# iridia-tam-main-board.net
KiCad netlist of a schematic drawn in EAGLE
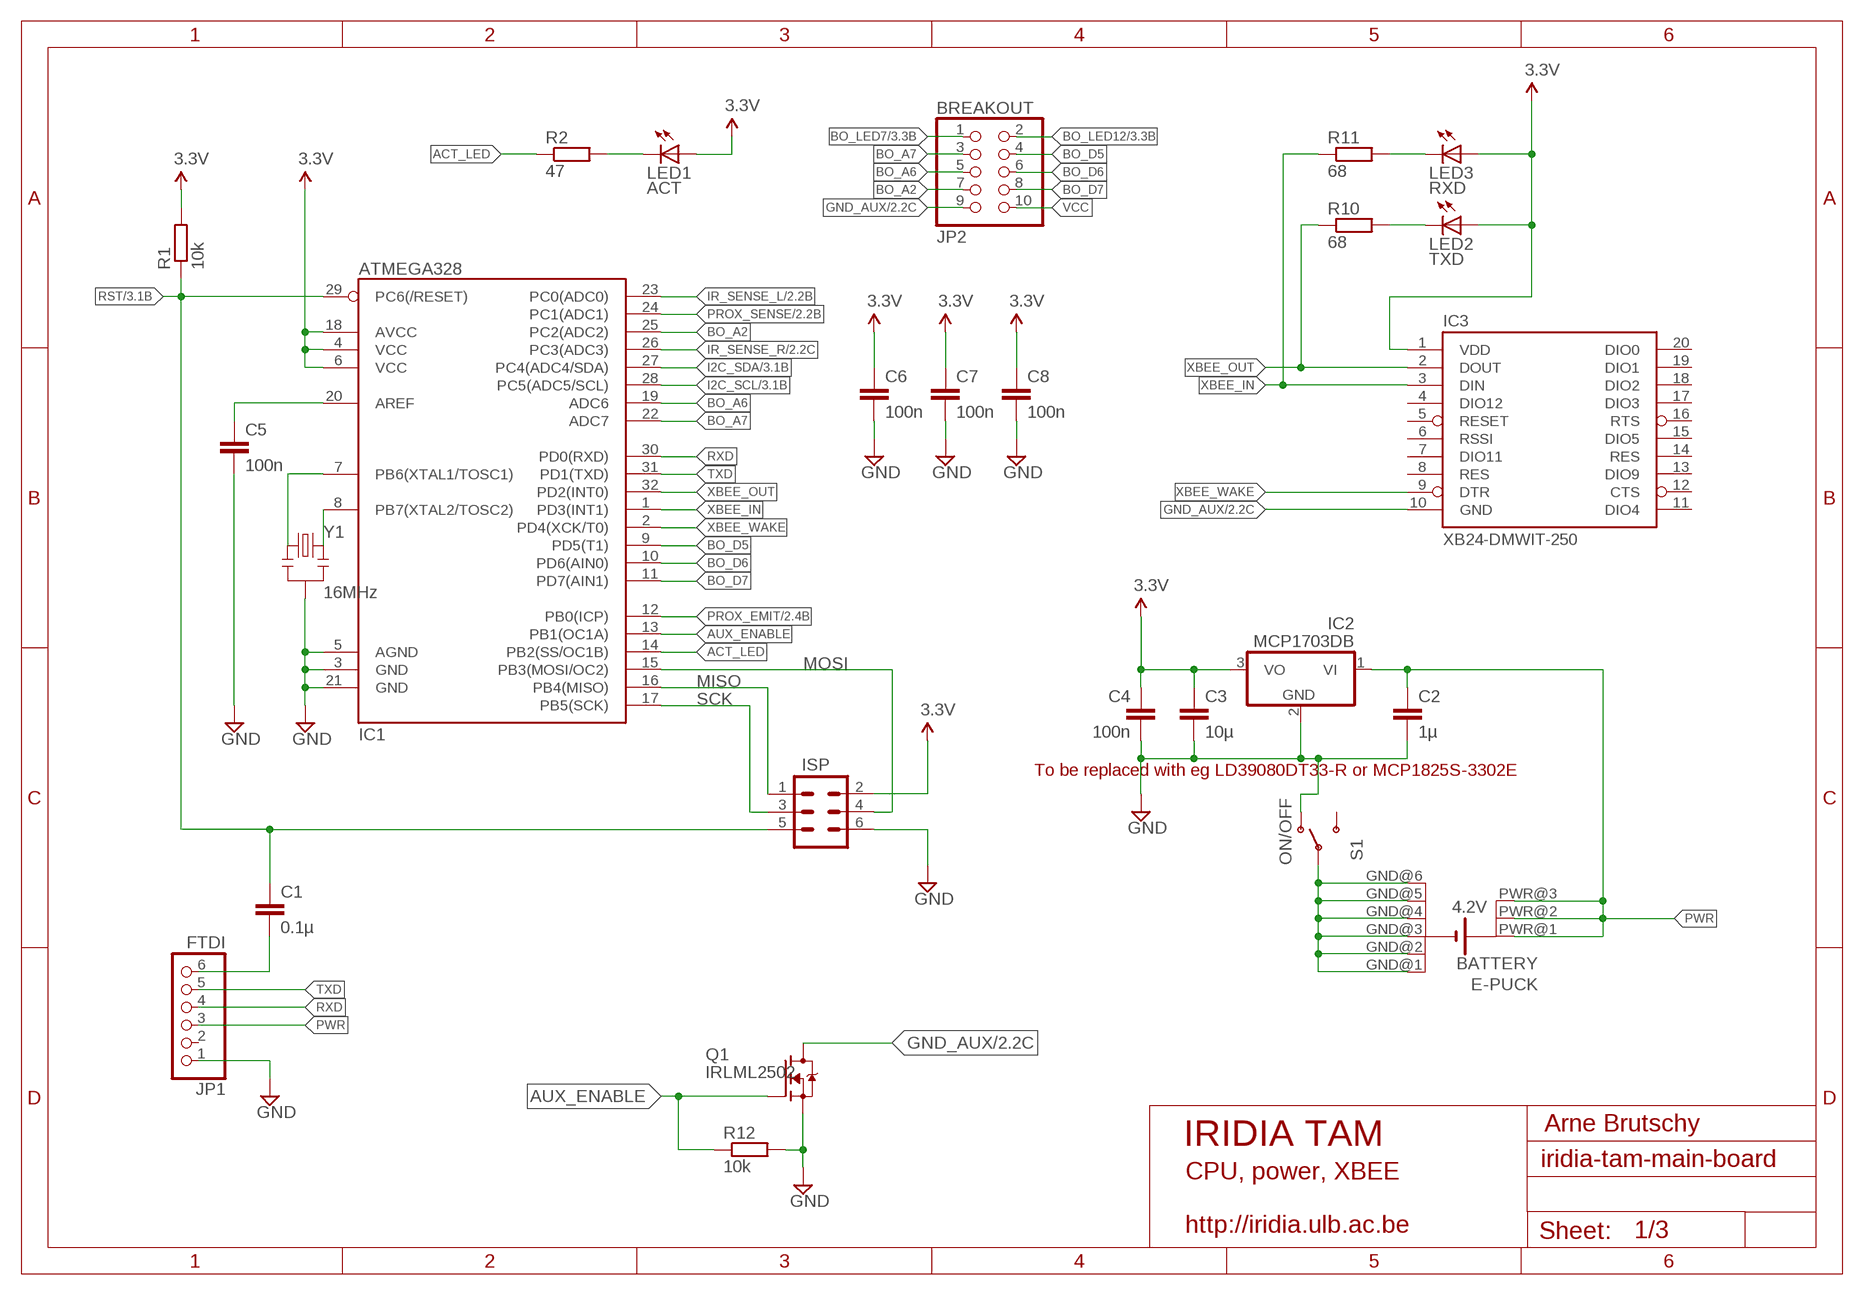
[diagram p0: schematic, sheet 1]
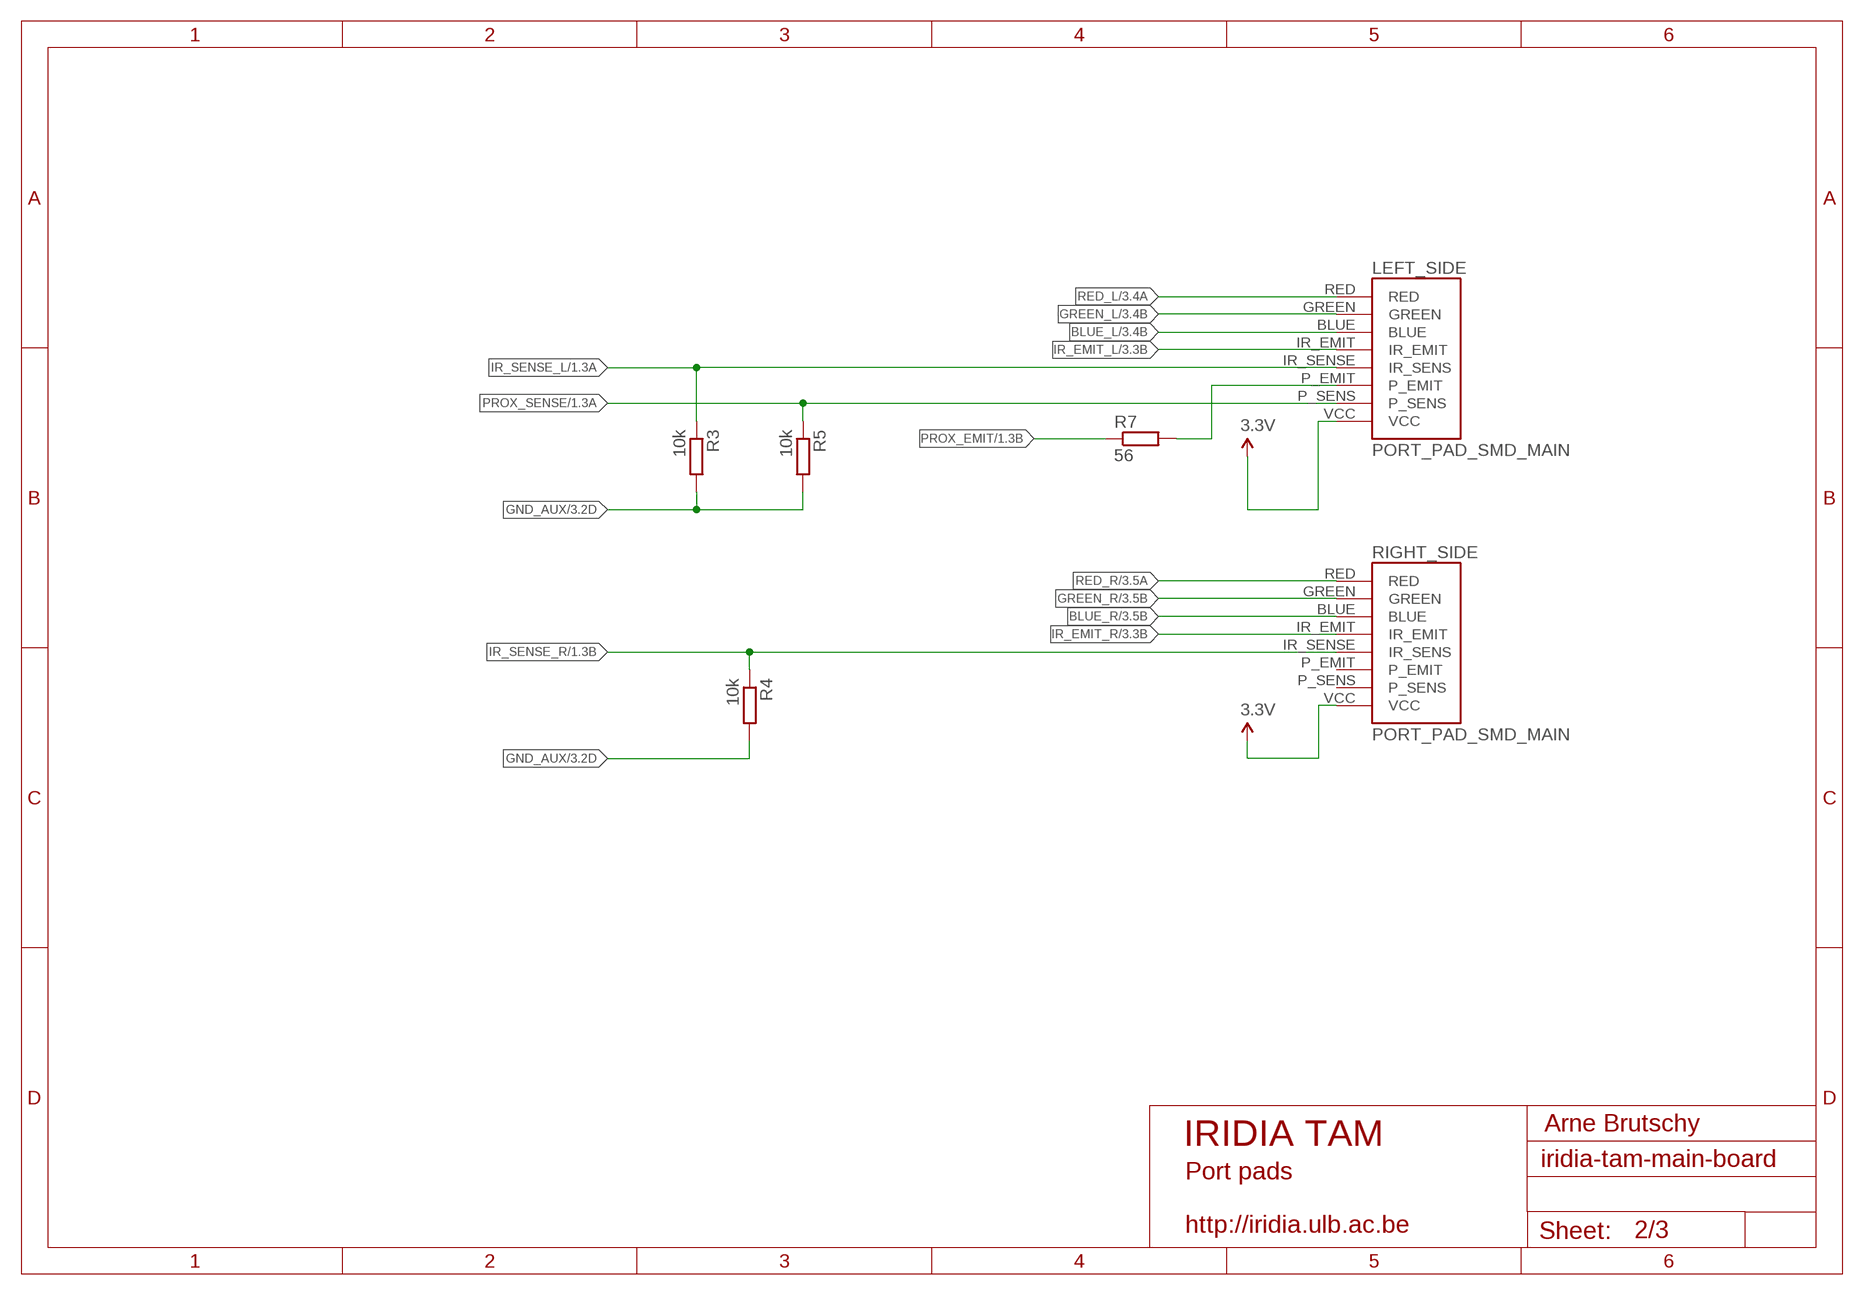
[diagram p1: schematic, sheet 2]
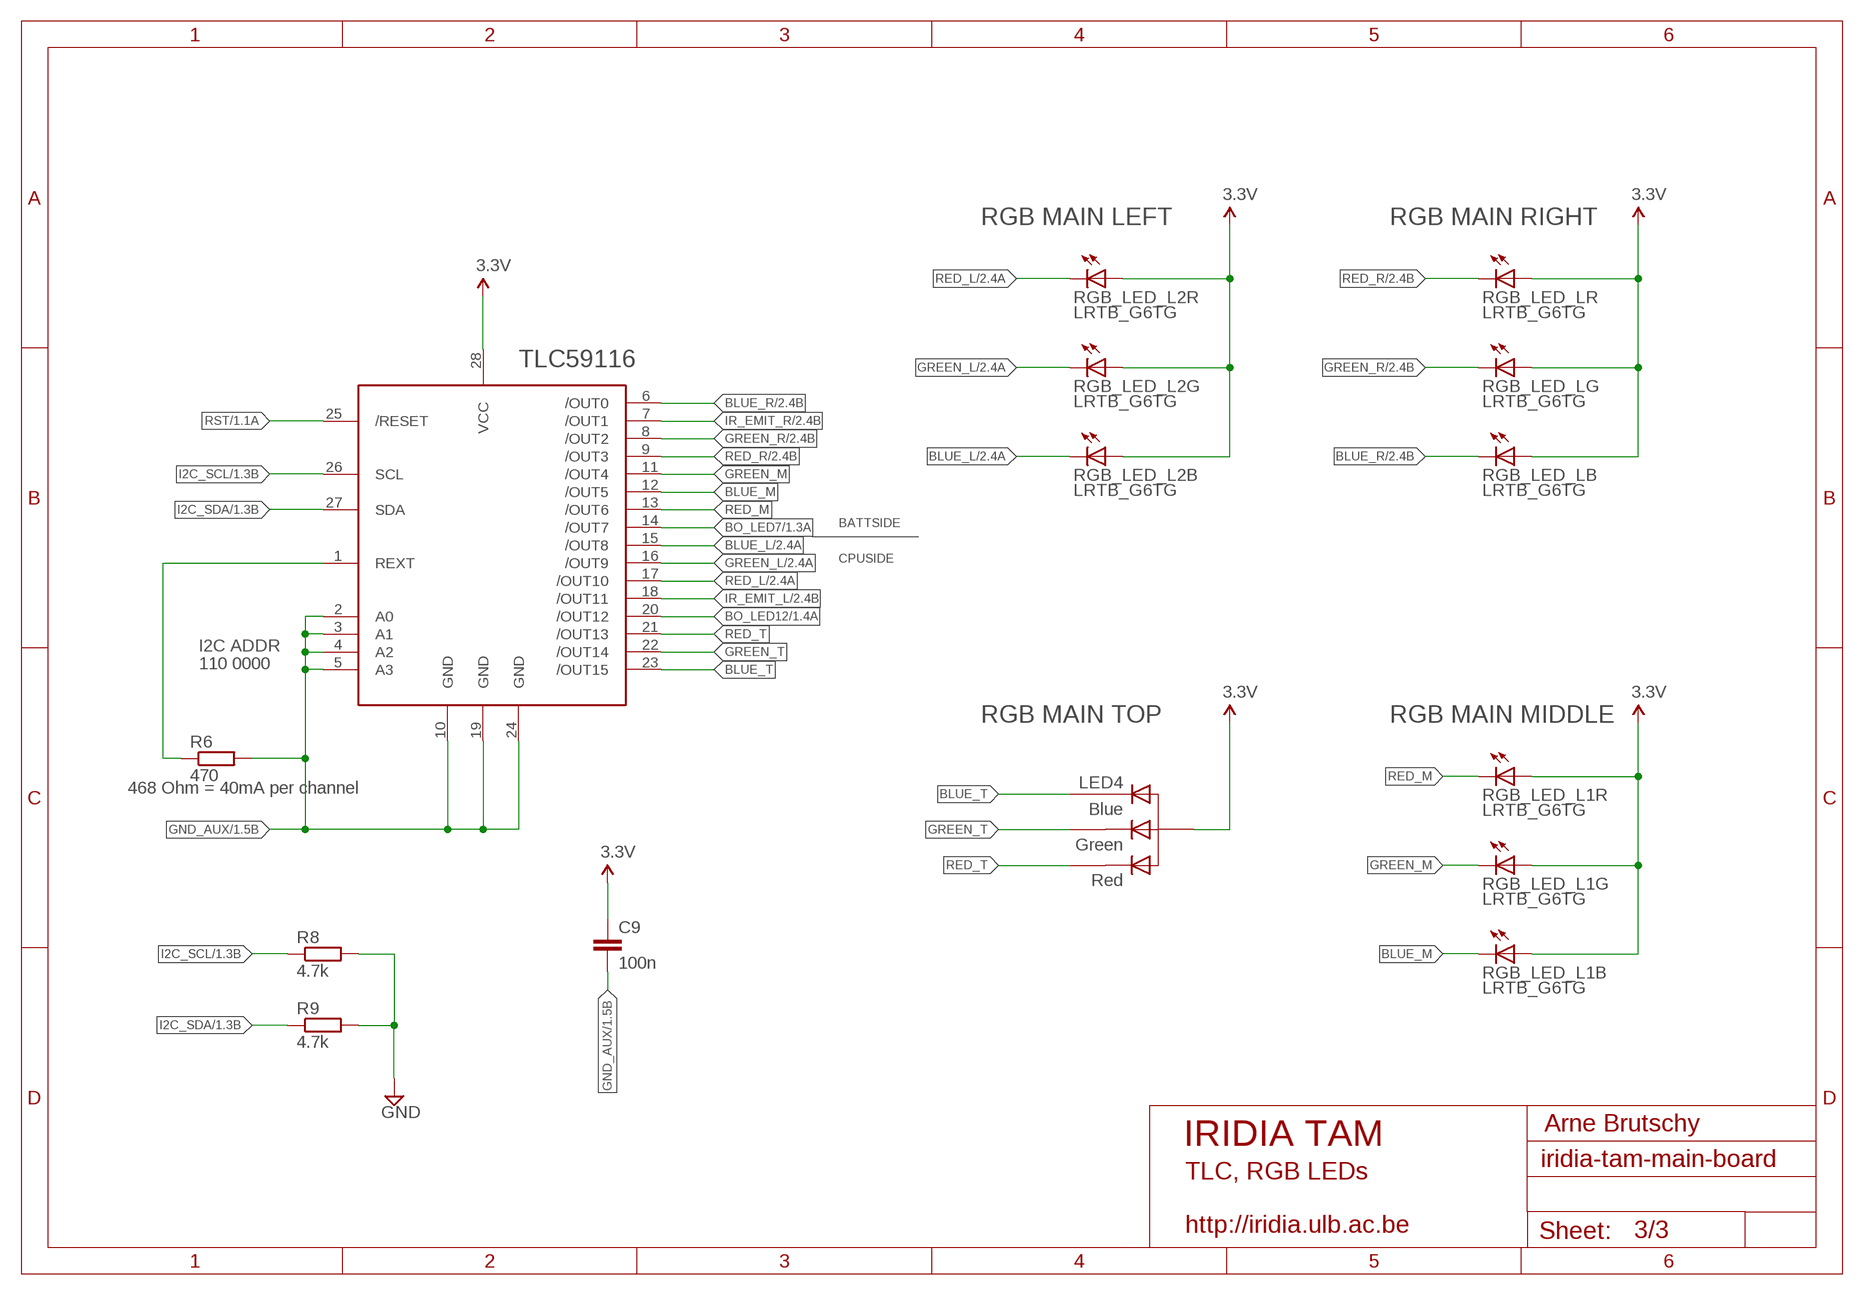
[diagram p2: schematic, sheet 3]

(export (version "E")
  (design (tool "Eeschema 10.0.6"))
  (components
    (comp (ref "C9")
      (value "100n")
      (footprint "eagle-import:0805")
      (libsource (lib "eagle-import") (part "CAP0805"))
    )
    (comp (ref "IC4")
      (value "TLC59116")
      (footprint "eagle-import:TSSOP28")
      (libsource (lib "eagle-import") (part "TLC59116"))
    )
    (comp (ref "LED4")
      (value "RGBLED_CA5MMTROUGHHOLE")
      (footprint "eagle-import:LED5MMRGB")
      (libsource (lib "eagle-import") (part "RGBLED_CA5MMTROUGHHOLE"))
    )
    (comp (ref "R6")
      (value "470")
      (footprint "eagle-import:R0805")
      (libsource (lib "eagle-import") (part "R-EU_R0805"))
    )
    (comp (ref "R8")
      (value "4.7k")
      (footprint "eagle-import:R0805")
      (libsource (lib "eagle-import") (part "R-EU_R0805"))
    )
    (comp (ref "R9")
      (value "4.7k")
      (footprint "eagle-import:R0805")
      (libsource (lib "eagle-import") (part "R-EU_R0805"))
    )
    (comp (ref "RGB_LED_L")
      (value "LRTB_G6TG")
      (footprint "eagle-import:P-LCC-6_TOPLED")
      (libsource (lib "eagle-import") (part "MULTILED_LRTB_G6TG"))
    )
    (comp (ref "RGB_LED_L1")
      (value "LRTB_G6TG")
      (footprint "eagle-import:P-LCC-6_TOPLED")
      (libsource (lib "eagle-import") (part "MULTILED_LRTB_G6TG"))
    )
    (comp (ref "RGB_LED_L2")
      (value "LRTB_G6TG")
      (footprint "eagle-import:P-LCC-6_TOPLED")
      (libsource (lib "eagle-import") (part "MULTILED_LRTB_G6TG"))
    )
    (comp (ref "BREAKOUT")
      (value "JP2")
      (footprint "eagle-import:2X05SMD")
      (libsource (lib "eagle-import") (part "PINHD-2X5_2.54-SMD"))
    )
    (comp (ref "C1")
      (value "0.1µ")
      (footprint "eagle-import:0805")
      (libsource (lib "eagle-import") (part "CAP0805"))
    )
    (comp (ref "C2")
      (value "1µ")
      (footprint "eagle-import:0805")
      (libsource (lib "eagle-import") (part "CAP0805"))
    )
    (comp (ref "C3")
      (value "10µ")
      (footprint "eagle-import:0805")
      (libsource (lib "eagle-import") (part "CAP0805"))
    )
    (comp (ref "C4")
      (value "100n")
      (footprint "eagle-import:0805")
      (libsource (lib "eagle-import") (part "CAP0805"))
    )
    (comp (ref "C5")
      (value "100n")
      (footprint "eagle-import:0805")
      (libsource (lib "eagle-import") (part "CAP0805"))
    )
    (comp (ref "C6")
      (value "100n")
      (footprint "eagle-import:0805")
      (libsource (lib "eagle-import") (part "CAP0805"))
    )
    (comp (ref "C7")
      (value "100n")
      (footprint "eagle-import:0805")
      (libsource (lib "eagle-import") (part "CAP0805"))
    )
    (comp (ref "C8")
      (value "100n")
      (footprint "eagle-import:0805")
      (libsource (lib "eagle-import") (part "CAP0805"))
    )
    (comp (ref "IC1")
      (value "ATMEGA328")
      (footprint "eagle-import:TQFP32-08")
      (libsource (lib "eagle-import") (part "ATMEGA168"))
    )
    (comp (ref "IC2")
      (value "MCP1703DB")
      (footprint "eagle-import:SOT223")
      (libsource (lib "eagle-import") (part "MCP1703DB"))
    )
    (comp (ref "IC3")
      (value "XB24-DMWIT-250")
      (footprint "eagle-import:XBEE-SMD")
      (libsource (lib "eagle-import") (part "XBEE-1B3"))
    )
    (comp (ref "JP1")
      (value "FTDI")
      (footprint "eagle-import:1X06SMD_90")
      (libsource (lib "eagle-import") (part "PINHD-1X6_2.54-SMD-90°"))
    )
    (comp (ref "LED1")
      (value "ACT")
      (footprint "eagle-import:LED-1206")
      (libsource (lib "eagle-import") (part "LED1206"))
    )
    (comp (ref "LED2")
      (value "TXD")
      (footprint "eagle-import:CHIPLED_0805")
      (libsource (lib "eagle-import") (part "LEDCHIPLED_0805"))
    )
    (comp (ref "LED3")
      (value "RXD")
      (footprint "eagle-import:CHIPLED_0805")
      (libsource (lib "eagle-import") (part "LEDCHIPLED_0805"))
    )
    (comp (ref "Q1")
      (value "IRLML2502")
      (footprint "eagle-import:SOT23-3")
      (libsource (lib "eagle-import") (part "IRLML2502"))
    )
    (comp (ref "R1")
      (value "10k")
      (footprint "eagle-import:R0805")
      (libsource (lib "eagle-import") (part "R-EU_R0805"))
    )
    (comp (ref "R2")
      (value "47")
      (footprint "eagle-import:R0805")
      (libsource (lib "eagle-import") (part "R-EU_R0805"))
    )
    (comp (ref "R10")
      (value "68")
      (footprint "eagle-import:R0805")
      (libsource (lib "eagle-import") (part "R-EU_R0805"))
    )
    (comp (ref "R11")
      (value "68")
      (footprint "eagle-import:R0805")
      (libsource (lib "eagle-import") (part "R-EU_R0805"))
    )
    (comp (ref "R12")
      (value "10k")
      (footprint "eagle-import:R0805")
      (libsource (lib "eagle-import") (part "R-EU_R0805"))
    )
    (comp (ref "S1")
      (value "ON/OFF")
      (footprint "eagle-import:200USP1T1A1M6RE")
      (libsource (lib "eagle-import") (part "TOGGLESW200MSP1T2B2M6RE"))
    )
    (comp (ref "SV1")
      (value "ISP")
      (footprint "eagle-import:MA03-2")
      (libsource (lib "eagle-import") (part "MA03-2"))
    )
    (comp (ref "U$4")
      (value "EPUCK_BATTERY")
      (footprint "eagle-import:EPUCK_BATTERY")
      (libsource (lib "eagle-import") (part "EPUCK_BATTERY"))
    )
    (comp (ref "Y1")
      (value "16MHz")
      (footprint "eagle-import:RESONATOR-SMD")
      (libsource (lib "eagle-import") (part "RESONATOR16MHZ"))
    )
    (comp (ref "LEFT_SIDE")
      (value "PORT_PAD_SMD_MAIN")
      (footprint "eagle-import:PORT_PAD_SMD_MAIN")
      (libsource (lib "eagle-import") (part "PORT_PAD_SMD_MAIN"))
    )
    (comp (ref "R3")
      (value "10k")
      (footprint "eagle-import:R0805")
      (libsource (lib "eagle-import") (part "R-EU_R0805"))
    )
    (comp (ref "R4")
      (value "10k")
      (footprint "eagle-import:R0805")
      (libsource (lib "eagle-import") (part "R-EU_R0805"))
    )
    (comp (ref "R5")
      (value "10k")
      (footprint "eagle-import:R0805")
      (libsource (lib "eagle-import") (part "R-EU_R0805"))
    )
    (comp (ref "R7")
      (value "56")
      (footprint "eagle-import:R0805")
      (libsource (lib "eagle-import") (part "R-EU_R0805"))
    )
    (comp (ref "RIGHT_SIDE")
      (value "PORT_PAD_SMD_MAIN")
      (footprint "eagle-import:PORT_PAD_SMD_MAIN")
      (libsource (lib "eagle-import") (part "PORT_PAD_SMD_MAIN"))
    )
  )
  (nets
    (net (code "1") (name "ACT_LED") (class "Default")
      (node (ref "IC1") (pin "14") (pinfunction "PB2(SS/OC1B)_14") (pintype "bidirectional"))
      (node (ref "R2") (pin "1") (pinfunction "1_1") (pintype "passive"))
    )
    (net (code "2") (name "AUX_ENABLE") (class "Default")
      (node (ref "IC1") (pin "13") (pinfunction "PB1(OC1A)_13") (pintype "bidirectional"))
      (node (ref "Q1") (pin "1") (pinfunction "G_1") (pintype "passive"))
      (node (ref "R12") (pin "1") (pinfunction "1_1") (pintype "passive"))
    )
    (net (code "3") (name "BLUE_L") (class "Default")
      (node (ref "IC4") (pin "15") (pinfunction "/OUT8_15") (pintype "bidirectional"))
      (node (ref "LEFT_SIDE") (pin "BLUE") (pinfunction "BLUE_BLUE") (pintype "bidirectional"))
      (node (ref "RGB_LED_L2") (pin "C3") (pinfunction "C_C3") (pintype "passive"))
    )
    (net (code "4") (name "BLUE_M") (class "Default")
      (node (ref "IC4") (pin "12") (pinfunction "/OUT5_12") (pintype "bidirectional"))
      (node (ref "RGB_LED_L1") (pin "C3") (pinfunction "C_C3") (pintype "passive"))
    )
    (net (code "5") (name "BLUE_R") (class "Default")
      (node (ref "IC4") (pin "6") (pinfunction "/OUT0_6") (pintype "bidirectional"))
      (node (ref "RGB_LED_L") (pin "C3") (pinfunction "C_C3") (pintype "passive"))
      (node (ref "RIGHT_SIDE") (pin "BLUE") (pinfunction "BLUE_BLUE") (pintype "bidirectional"))
    )
    (net (code "6") (name "BLUE_T") (class "Default")
      (node (ref "IC4") (pin "23") (pinfunction "/OUT15_23") (pintype "bidirectional"))
      (node (ref "LED4") (pin "4") (pinfunction "CB_4") (pintype "bidirectional"))
    )
    (net (code "7") (name "BO_A2") (class "Default")
      (node (ref "BREAKOUT") (pin "7") (pinfunction "7_7") (pintype "passive"))
      (node (ref "IC1") (pin "25") (pinfunction "PC2(ADC2)_25") (pintype "bidirectional"))
    )
    (net (code "8") (name "BO_A6") (class "Default")
      (node (ref "BREAKOUT") (pin "5") (pinfunction "5_5") (pintype "passive"))
      (node (ref "IC1") (pin "19") (pinfunction "ADC6_19") (pintype "bidirectional"))
    )
    (net (code "9") (name "BO_A7") (class "Default")
      (node (ref "BREAKOUT") (pin "3") (pinfunction "3_3") (pintype "passive"))
      (node (ref "IC1") (pin "22") (pinfunction "ADC7_22") (pintype "bidirectional"))
    )
    (net (code "10") (name "BO_D5") (class "Default")
      (node (ref "BREAKOUT") (pin "4") (pinfunction "4_4") (pintype "passive"))
      (node (ref "IC1") (pin "9") (pinfunction "PD5(T1)_9") (pintype "bidirectional"))
    )
    (net (code "11") (name "BO_D6") (class "Default")
      (node (ref "BREAKOUT") (pin "6") (pinfunction "6_6") (pintype "passive"))
      (node (ref "IC1") (pin "10") (pinfunction "PD6(AIN0)_10") (pintype "bidirectional"))
    )
    (net (code "12") (name "BO_D7") (class "Default")
      (node (ref "BREAKOUT") (pin "8") (pinfunction "8_8") (pintype "passive"))
      (node (ref "IC1") (pin "11") (pinfunction "PD7(AIN1)_11") (pintype "bidirectional"))
    )
    (net (code "13") (name "BO_LED7") (class "Default")
      (node (ref "BREAKOUT") (pin "1") (pinfunction "1_1") (pintype "passive"))
      (node (ref "IC4") (pin "14") (pinfunction "/OUT7_14") (pintype "bidirectional"))
    )
    (net (code "14") (name "BO_LED12") (class "Default")
      (node (ref "BREAKOUT") (pin "2") (pinfunction "2_2") (pintype "passive"))
      (node (ref "IC4") (pin "20") (pinfunction "/OUT12_20") (pintype "bidirectional"))
    )
    (net (code "15") (name "GND") (class "Default")
      (node (ref "C2") (pin "2") (pinfunction "2_2") (pintype "passive"))
      (node (ref "C3") (pin "2") (pinfunction "2_2") (pintype "passive"))
      (node (ref "C4") (pin "2") (pinfunction "2_2") (pintype "passive"))
      (node (ref "C5") (pin "2") (pinfunction "2_2") (pintype "passive"))
      (node (ref "C6") (pin "2") (pinfunction "2_2") (pintype "passive"))
      (node (ref "C7") (pin "2") (pinfunction "2_2") (pintype "passive"))
      (node (ref "C8") (pin "2") (pinfunction "2_2") (pintype "passive"))
      (node (ref "IC1") (pin "21") (pinfunction "GND_21") (pintype "bidirectional"))
      (node (ref "IC1") (pin "3") (pinfunction "GND_3") (pintype "bidirectional"))
      (node (ref "IC1") (pin "5") (pinfunction "AGND_5") (pintype "bidirectional"))
      (node (ref "IC2") (pin "2") (pinfunction "GND_2") (pintype "passive"))
      (node (ref "JP1") (pin "1") (pinfunction "1_1") (pintype "passive"))
      (node (ref "Q1") (pin "2") (pinfunction "S_2") (pintype "passive"))
      (node (ref "R12") (pin "2") (pinfunction "2_2") (pintype "passive"))
      (node (ref "R8") (pin "2") (pinfunction "2_2") (pintype "passive"))
      (node (ref "R9") (pin "2") (pinfunction "2_2") (pintype "passive"))
      (node (ref "S1") (pin "A") (pinfunction "A_A") (pintype "passive"))
      (node (ref "SV1") (pin "6") (pinfunction "6_6") (pintype "passive"))
      (node (ref "Y1") (pin "2") (pinfunction "2_2") (pintype "passive"))
    )
    (net (code "16") (name "GND_AUX") (class "Default")
      (node (ref "BREAKOUT") (pin "9") (pinfunction "9_9") (pintype "passive"))
      (node (ref "C9") (pin "2") (pinfunction "2_2") (pintype "passive"))
      (node (ref "IC3") (pin "10") (pinfunction "GND_10") (pintype "power_in"))
      (node (ref "IC4") (pin "10") (pinfunction "GND_10") (pintype "bidirectional"))
      (node (ref "IC4") (pin "19") (pinfunction "GND_19") (pintype "bidirectional"))
      (node (ref "IC4") (pin "2") (pinfunction "A0_2") (pintype "bidirectional"))
      (node (ref "IC4") (pin "24") (pinfunction "GND_24") (pintype "bidirectional"))
      (node (ref "IC4") (pin "3") (pinfunction "A1_3") (pintype "bidirectional"))
      (node (ref "IC4") (pin "4") (pinfunction "A2_4") (pintype "bidirectional"))
      (node (ref "IC4") (pin "5") (pinfunction "A3_5") (pintype "bidirectional"))
      (node (ref "Q1") (pin "3") (pinfunction "D_3") (pintype "passive"))
      (node (ref "R3") (pin "2") (pinfunction "2_2") (pintype "passive"))
      (node (ref "R4") (pin "2") (pinfunction "2_2") (pintype "passive"))
      (node (ref "R5") (pin "2") (pinfunction "2_2") (pintype "passive"))
      (node (ref "R6") (pin "2") (pinfunction "2_2") (pintype "passive"))
    )
    (net (code "17") (name "GREEN_L") (class "Default")
      (node (ref "IC4") (pin "16") (pinfunction "/OUT9_16") (pintype "bidirectional"))
      (node (ref "LEFT_SIDE") (pin "GREEN") (pinfunction "GREEN_GREEN") (pintype "bidirectional"))
      (node (ref "RGB_LED_L2") (pin "C2") (pinfunction "C_C2") (pintype "passive"))
    )
    (net (code "18") (name "GREEN_M") (class "Default")
      (node (ref "IC4") (pin "11") (pinfunction "/OUT4_11") (pintype "bidirectional"))
      (node (ref "RGB_LED_L1") (pin "C2") (pinfunction "C_C2") (pintype "passive"))
    )
    (net (code "19") (name "GREEN_R") (class "Default")
      (node (ref "IC4") (pin "8") (pinfunction "/OUT2_8") (pintype "bidirectional"))
      (node (ref "RGB_LED_L") (pin "C2") (pinfunction "C_C2") (pintype "passive"))
      (node (ref "RIGHT_SIDE") (pin "GREEN") (pinfunction "GREEN_GREEN") (pintype "bidirectional"))
    )
    (net (code "20") (name "GREEN_T") (class "Default")
      (node (ref "IC4") (pin "22") (pinfunction "/OUT14_22") (pintype "bidirectional"))
      (node (ref "LED4") (pin "3") (pinfunction "CG_3") (pintype "bidirectional"))
    )
    (net (code "21") (name "I2C_SCL") (class "Default")
      (node (ref "IC1") (pin "28") (pinfunction "PC5(ADC5/SCL)_28") (pintype "bidirectional"))
      (node (ref "IC4") (pin "26") (pinfunction "SCL_26") (pintype "bidirectional"))
      (node (ref "R8") (pin "1") (pinfunction "1_1") (pintype "passive"))
    )
    (net (code "22") (name "I2C_SDA") (class "Default")
      (node (ref "IC1") (pin "27") (pinfunction "PC4(ADC4/SDA)_27") (pintype "bidirectional"))
      (node (ref "IC4") (pin "27") (pinfunction "SDA_27") (pintype "bidirectional"))
      (node (ref "R9") (pin "1") (pinfunction "1_1") (pintype "passive"))
    )
    (net (code "23") (name "IR_EMIT_L") (class "Default")
      (node (ref "IC4") (pin "18") (pinfunction "/OUT11_18") (pintype "bidirectional"))
      (node (ref "LEFT_SIDE") (pin "IR_EMIT") (pinfunction "IR_EMIT_IR_EMIT") (pintype "bidirectional"))
    )
    (net (code "24") (name "IR_EMIT_R") (class "Default")
      (node (ref "IC4") (pin "7") (pinfunction "/OUT1_7") (pintype "bidirectional"))
      (node (ref "RIGHT_SIDE") (pin "IR_EMIT") (pinfunction "IR_EMIT_IR_EMIT") (pintype "bidirectional"))
    )
    (net (code "25") (name "IR_SENSE_L") (class "Default")
      (node (ref "IC1") (pin "23") (pinfunction "PC0(ADC0)_23") (pintype "bidirectional"))
      (node (ref "LEFT_SIDE") (pin "IR_SENSE") (pinfunction "IR_SENS_IR_SENSE") (pintype "bidirectional"))
      (node (ref "R3") (pin "1") (pinfunction "1_1") (pintype "passive"))
    )
    (net (code "26") (name "IR_SENSE_R") (class "Default")
      (node (ref "IC1") (pin "26") (pinfunction "PC3(ADC3)_26") (pintype "bidirectional"))
      (node (ref "R4") (pin "1") (pinfunction "1_1") (pintype "passive"))
      (node (ref "RIGHT_SIDE") (pin "IR_SENSE") (pinfunction "IR_SENS_IR_SENSE") (pintype "bidirectional"))
    )
    (net (code "27") (name "MISO") (class "Default")
      (node (ref "IC1") (pin "16") (pinfunction "PB4(MISO)_16") (pintype "bidirectional"))
      (node (ref "SV1") (pin "1") (pinfunction "1_1") (pintype "passive"))
    )
    (net (code "28") (name "MOSI") (class "Default")
      (node (ref "IC1") (pin "15") (pinfunction "PB3(MOSI/OC2)_15") (pintype "bidirectional"))
      (node (ref "SV1") (pin "4") (pinfunction "4_4") (pintype "passive"))
    )
    (net (code "29") (name "Net-(C1-Pad2)") (class "Default")
      (node (ref "C1") (pin "2") (pinfunction "2_2") (pintype "passive"))
      (node (ref "JP1") (pin "6") (pinfunction "6_6") (pintype "passive"))
    )
    (net (code "30") (name "Net-(IC1-AREF)") (class "Default")
      (node (ref "C5") (pin "1") (pinfunction "1_1") (pintype "passive"))
      (node (ref "IC1") (pin "20") (pinfunction "AREF_20") (pintype "bidirectional"))
    )
    (net (code "31") (name "Net-(IC1-PB6(XTAL1{slash}TOSC1))") (class "Default")
      (node (ref "IC1") (pin "7") (pinfunction "PB6(XTAL1/TOSC1)_7") (pintype "bidirectional"))
      (node (ref "Y1") (pin "1") (pinfunction "1_1") (pintype "passive"))
    )
    (net (code "32") (name "Net-(IC1-PB7(XTAL2{slash}TOSC2))") (class "Default")
      (node (ref "IC1") (pin "8") (pinfunction "PB7(XTAL2/TOSC2)_8") (pintype "bidirectional"))
      (node (ref "Y1") (pin "3") (pinfunction "3_3") (pintype "passive"))
    )
    (net (code "33") (name "Net-(IC4-REXT)") (class "Default")
      (node (ref "IC4") (pin "1") (pinfunction "REXT_1") (pintype "bidirectional"))
      (node (ref "R6") (pin "1") (pinfunction "1_1") (pintype "passive"))
    )
    (net (code "34") (name "Net-(LED1-PadC)") (class "Default")
      (node (ref "LED1") (pin "C") (pinfunction "C_C") (pintype "passive"))
      (node (ref "R2") (pin "2") (pinfunction "2_2") (pintype "passive"))
    )
    (net (code "35") (name "Net-(LED2-PadC)") (class "Default")
      (node (ref "LED2") (pin "C") (pinfunction "C_C") (pintype "passive"))
      (node (ref "R10") (pin "2") (pinfunction "2_2") (pintype "passive"))
    )
    (net (code "36") (name "Net-(LED3-PadC)") (class "Default")
      (node (ref "LED3") (pin "C") (pinfunction "C_C") (pintype "passive"))
      (node (ref "R11") (pin "2") (pinfunction "2_2") (pintype "passive"))
    )
    (net (code "37") (name "Net-(LEFT_SIDE-PadP_EMIT)") (class "Default")
      (node (ref "LEFT_SIDE") (pin "P_EMIT") (pinfunction "P_EMIT_P_EMIT") (pintype "bidirectional"))
      (node (ref "R7") (pin "2") (pinfunction "2_2") (pintype "passive"))
    )
    (net (code "38") (name "Net-(U$4--1)") (class "Default")
      (node (ref "S1") (pin "COM") (pinfunction "COM_COM") (pintype "passive"))
      (node (ref "U$4") (pin "GND@1") (pinfunction "-1_GND@1") (pintype "power_in"))
      (node (ref "U$4") (pin "GND@2") (pinfunction "-2_GND@2") (pintype "power_in"))
      (node (ref "U$4") (pin "GND@3") (pinfunction "-3_GND@3") (pintype "power_in"))
      (node (ref "U$4") (pin "GND@4") (pinfunction "-4_GND@4") (pintype "power_in"))
      (node (ref "U$4") (pin "GND@5") (pinfunction "-5_GND@5") (pintype "power_in"))
      (node (ref "U$4") (pin "GND@6") (pinfunction "-6_GND@6") (pintype "power_in"))
    )
    (net (code "39") (name "PROX_EMIT") (class "Default")
      (node (ref "IC1") (pin "12") (pinfunction "PB0(ICP)_12") (pintype "bidirectional"))
      (node (ref "R7") (pin "1") (pinfunction "1_1") (pintype "passive"))
    )
    (net (code "40") (name "PROX_SENSE") (class "Default")
      (node (ref "IC1") (pin "24") (pinfunction "PC1(ADC1)_24") (pintype "bidirectional"))
      (node (ref "LEFT_SIDE") (pin "P_SENS") (pinfunction "P_SENS_P_SENS") (pintype "bidirectional"))
      (node (ref "R5") (pin "1") (pinfunction "1_1") (pintype "passive"))
    )
    (net (code "41") (name "PWR") (class "Default")
      (node (ref "C2") (pin "1") (pinfunction "1_1") (pintype "passive"))
      (node (ref "IC2") (pin "1") (pinfunction "VI_1") (pintype "input"))
      (node (ref "JP1") (pin "3") (pinfunction "3_3") (pintype "passive"))
      (node (ref "U$4") (pin "PWR@1") (pinfunction "+1_PWR@1") (pintype "power_in"))
      (node (ref "U$4") (pin "PWR@2") (pinfunction "+2_PWR@2") (pintype "power_in"))
      (node (ref "U$4") (pin "PWR@3") (pinfunction "+3_PWR@3") (pintype "power_in"))
    )
    (net (code "42") (name "RED_L") (class "Default")
      (node (ref "IC4") (pin "17") (pinfunction "/OUT10_17") (pintype "bidirectional"))
      (node (ref "LEFT_SIDE") (pin "RED") (pinfunction "RED_RED") (pintype "bidirectional"))
      (node (ref "RGB_LED_L2") (pin "C1") (pinfunction "C_C1") (pintype "passive"))
    )
    (net (code "43") (name "RED_M") (class "Default")
      (node (ref "IC4") (pin "13") (pinfunction "/OUT6_13") (pintype "bidirectional"))
      (node (ref "RGB_LED_L1") (pin "C1") (pinfunction "C_C1") (pintype "passive"))
    )
    (net (code "44") (name "RED_R") (class "Default")
      (node (ref "IC4") (pin "9") (pinfunction "/OUT3_9") (pintype "bidirectional"))
      (node (ref "RGB_LED_L") (pin "C1") (pinfunction "C_C1") (pintype "passive"))
      (node (ref "RIGHT_SIDE") (pin "RED") (pinfunction "RED_RED") (pintype "bidirectional"))
    )
    (net (code "45") (name "RED_T") (class "Default")
      (node (ref "IC4") (pin "21") (pinfunction "/OUT13_21") (pintype "bidirectional"))
      (node (ref "LED4") (pin "1") (pinfunction "CR_1") (pintype "bidirectional"))
    )
    (net (code "46") (name "RST") (class "Default")
      (node (ref "C1") (pin "1") (pinfunction "1_1") (pintype "passive"))
      (node (ref "IC1") (pin "29") (pinfunction "PC6(/RESET)_29") (pintype "bidirectional"))
      (node (ref "IC4") (pin "25") (pinfunction "/RESET_25") (pintype "bidirectional"))
      (node (ref "R1") (pin "1") (pinfunction "1_1") (pintype "passive"))
      (node (ref "SV1") (pin "5") (pinfunction "5_5") (pintype "passive"))
    )
    (net (code "47") (name "RXD") (class "Default")
      (node (ref "IC1") (pin "30") (pinfunction "PD0(RXD)_30") (pintype "bidirectional"))
      (node (ref "JP1") (pin "4") (pinfunction "4_4") (pintype "passive"))
    )
    (net (code "48") (name "SCK") (class "Default")
      (node (ref "IC1") (pin "17") (pinfunction "PB5(SCK)_17") (pintype "bidirectional"))
      (node (ref "SV1") (pin "3") (pinfunction "3_3") (pintype "passive"))
    )
    (net (code "49") (name "TXD") (class "Default")
      (node (ref "IC1") (pin "31") (pinfunction "PD1(TXD)_31") (pintype "bidirectional"))
      (node (ref "JP1") (pin "5") (pinfunction "5_5") (pintype "passive"))
    )
    (net (code "50") (name "VCC") (class "Default")
      (node (ref "BREAKOUT") (pin "10") (pinfunction "10_10") (pintype "passive"))
      (node (ref "C3") (pin "1") (pinfunction "1_1") (pintype "passive"))
      (node (ref "C4") (pin "1") (pinfunction "1_1") (pintype "passive"))
      (node (ref "C6") (pin "1") (pinfunction "1_1") (pintype "passive"))
      (node (ref "C7") (pin "1") (pinfunction "1_1") (pintype "passive"))
      (node (ref "C8") (pin "1") (pinfunction "1_1") (pintype "passive"))
      (node (ref "C9") (pin "1") (pinfunction "1_1") (pintype "passive"))
      (node (ref "IC1") (pin "18") (pinfunction "AVCC_18") (pintype "bidirectional"))
      (node (ref "IC1") (pin "4") (pinfunction "VCC_4") (pintype "bidirectional"))
      (node (ref "IC1") (pin "6") (pinfunction "VCC_6") (pintype "bidirectional"))
      (node (ref "IC2") (pin "3") (pinfunction "VO_3") (pintype "passive"))
      (node (ref "IC3") (pin "1") (pinfunction "VDD_1") (pintype "power_in"))
      (node (ref "IC4") (pin "28") (pinfunction "VCC_28") (pintype "bidirectional"))
      (node (ref "LED1") (pin "A") (pinfunction "A_A") (pintype "passive"))
      (node (ref "LED2") (pin "A") (pinfunction "A_A") (pintype "passive"))
      (node (ref "LED3") (pin "A") (pinfunction "A_A") (pintype "passive"))
      (node (ref "LED4") (pin "2") (pinfunction "A_2") (pintype "bidirectional"))
      (node (ref "LEFT_SIDE") (pin "VCC") (pinfunction "VCC_VCC") (pintype "bidirectional"))
      (node (ref "R1") (pin "2") (pinfunction "2_2") (pintype "passive"))
      (node (ref "RGB_LED_L") (pin "A1") (pinfunction "A_A1") (pintype "passive"))
      (node (ref "RGB_LED_L") (pin "A2") (pinfunction "A_A2") (pintype "passive"))
      (node (ref "RGB_LED_L") (pin "A3") (pinfunction "A_A3") (pintype "passive"))
      (node (ref "RGB_LED_L1") (pin "A1") (pinfunction "A_A1") (pintype "passive"))
      (node (ref "RGB_LED_L1") (pin "A2") (pinfunction "A_A2") (pintype "passive"))
      (node (ref "RGB_LED_L1") (pin "A3") (pinfunction "A_A3") (pintype "passive"))
      (node (ref "RGB_LED_L2") (pin "A1") (pinfunction "A_A1") (pintype "passive"))
      (node (ref "RGB_LED_L2") (pin "A2") (pinfunction "A_A2") (pintype "passive"))
      (node (ref "RGB_LED_L2") (pin "A3") (pinfunction "A_A3") (pintype "passive"))
      (node (ref "RIGHT_SIDE") (pin "VCC") (pinfunction "VCC_VCC") (pintype "bidirectional"))
      (node (ref "SV1") (pin "2") (pinfunction "2_2") (pintype "passive"))
    )
    (net (code "51") (name "XBEE_IN") (class "Default")
      (node (ref "IC1") (pin "1") (pinfunction "PD3(INT1)_1") (pintype "bidirectional"))
      (node (ref "IC3") (pin "3") (pinfunction "DIN_3") (pintype "input"))
      (node (ref "R11") (pin "1") (pinfunction "1_1") (pintype "passive"))
    )
    (net (code "52") (name "XBEE_OUT") (class "Default")
      (node (ref "IC1") (pin "32") (pinfunction "PD2(INT0)_32") (pintype "bidirectional"))
      (node (ref "IC3") (pin "2") (pinfunction "DOUT_2") (pintype "output"))
      (node (ref "R10") (pin "1") (pinfunction "1_1") (pintype "passive"))
    )
    (net (code "53") (name "XBEE_WAKE") (class "Default")
      (node (ref "IC1") (pin "2") (pinfunction "PD4(XCK/T0)_2") (pintype "bidirectional"))
      (node (ref "IC3") (pin "9") (pinfunction "DTR_9") (pintype "bidirectional"))
    )
    (net (code "54") (name "unconnected-(IC3-CTS-Pad12)") (class "Default")
      (node (ref "IC3") (pin "12") (pinfunction "CTS_12") (pintype "output"))
    )
    (net (code "55") (name "unconnected-(IC3-DIO0-Pad20)") (class "Default")
      (node (ref "IC3") (pin "20") (pinfunction "DIO0_20") (pintype "bidirectional"))
    )
    (net (code "56") (name "unconnected-(IC3-DIO1-Pad19)") (class "Default")
      (node (ref "IC3") (pin "19") (pinfunction "DIO1_19") (pintype "bidirectional"))
    )
    (net (code "57") (name "unconnected-(IC3-DIO2-Pad18)") (class "Default")
      (node (ref "IC3") (pin "18") (pinfunction "DIO2_18") (pintype "bidirectional"))
    )
    (net (code "58") (name "unconnected-(IC3-DIO3-Pad17)") (class "Default")
      (node (ref "IC3") (pin "17") (pinfunction "DIO3_17") (pintype "bidirectional"))
    )
    (net (code "59") (name "unconnected-(IC3-DIO4-Pad11)") (class "Default")
      (node (ref "IC3") (pin "11") (pinfunction "DIO4_11") (pintype "bidirectional"))
    )
    (net (code "60") (name "unconnected-(IC3-DIO5-Pad15)") (class "Default")
      (node (ref "IC3") (pin "15") (pinfunction "DIO5_15") (pintype "bidirectional"))
    )
    (net (code "61") (name "unconnected-(IC3-DIO9-Pad13)") (class "Default")
      (node (ref "IC3") (pin "13") (pinfunction "DIO9_13") (pintype "bidirectional"))
    )
    (net (code "62") (name "unconnected-(IC3-DIO11-Pad7)") (class "Default")
      (node (ref "IC3") (pin "7") (pinfunction "DIO11_7") (pintype "bidirectional"))
    )
    (net (code "63") (name "unconnected-(IC3-DIO12-Pad4)") (class "Default")
      (node (ref "IC3") (pin "4") (pinfunction "DIO12_4") (pintype "bidirectional"))
    )
    (net (code "64") (name "unconnected-(IC3-RES-Pad8)") (class "Default")
      (node (ref "IC3") (pin "8") (pinfunction "RES_8") (pintype "bidirectional"))
    )
    (net (code "65") (name "unconnected-(IC3-RES-Pad14)") (class "Default")
      (node (ref "IC3") (pin "14") (pinfunction "RES_14") (pintype "bidirectional"))
    )
    (net (code "66") (name "unconnected-(IC3-RESET-Pad5)") (class "Default")
      (node (ref "IC3") (pin "5") (pinfunction "RESET_5") (pintype "input"))
    )
    (net (code "67") (name "unconnected-(IC3-RSSI-Pad6)") (class "Default")
      (node (ref "IC3") (pin "6") (pinfunction "RSSI_6") (pintype "bidirectional"))
    )
    (net (code "68") (name "unconnected-(IC3-RTS-Pad16)") (class "Default")
      (node (ref "IC3") (pin "16") (pinfunction "RTS_16") (pintype "input"))
    )
    (net (code "69") (name "unconnected-(JP1-Pad2)") (class "Default")
      (node (ref "JP1") (pin "2") (pinfunction "2_2") (pintype "passive"))
    )
    (net (code "70") (name "unconnected-(RIGHT_SIDE-PadP_EMIT)") (class "Default")
      (node (ref "RIGHT_SIDE") (pin "P_EMIT") (pinfunction "P_EMIT_P_EMIT") (pintype "bidirectional"))
    )
    (net (code "71") (name "unconnected-(RIGHT_SIDE-PadP_SENS)") (class "Default")
      (node (ref "RIGHT_SIDE") (pin "P_SENS") (pinfunction "P_SENS_P_SENS") (pintype "bidirectional"))
    )
    (net (code "72") (name "unconnected-(S1-PadB)") (class "Default")
      (node (ref "S1") (pin "B") (pinfunction "B_B") (pintype "passive"))
    )
  )
)
